# Sheet1.net
KiCad netlist of a schematic drawn in Altium Designer
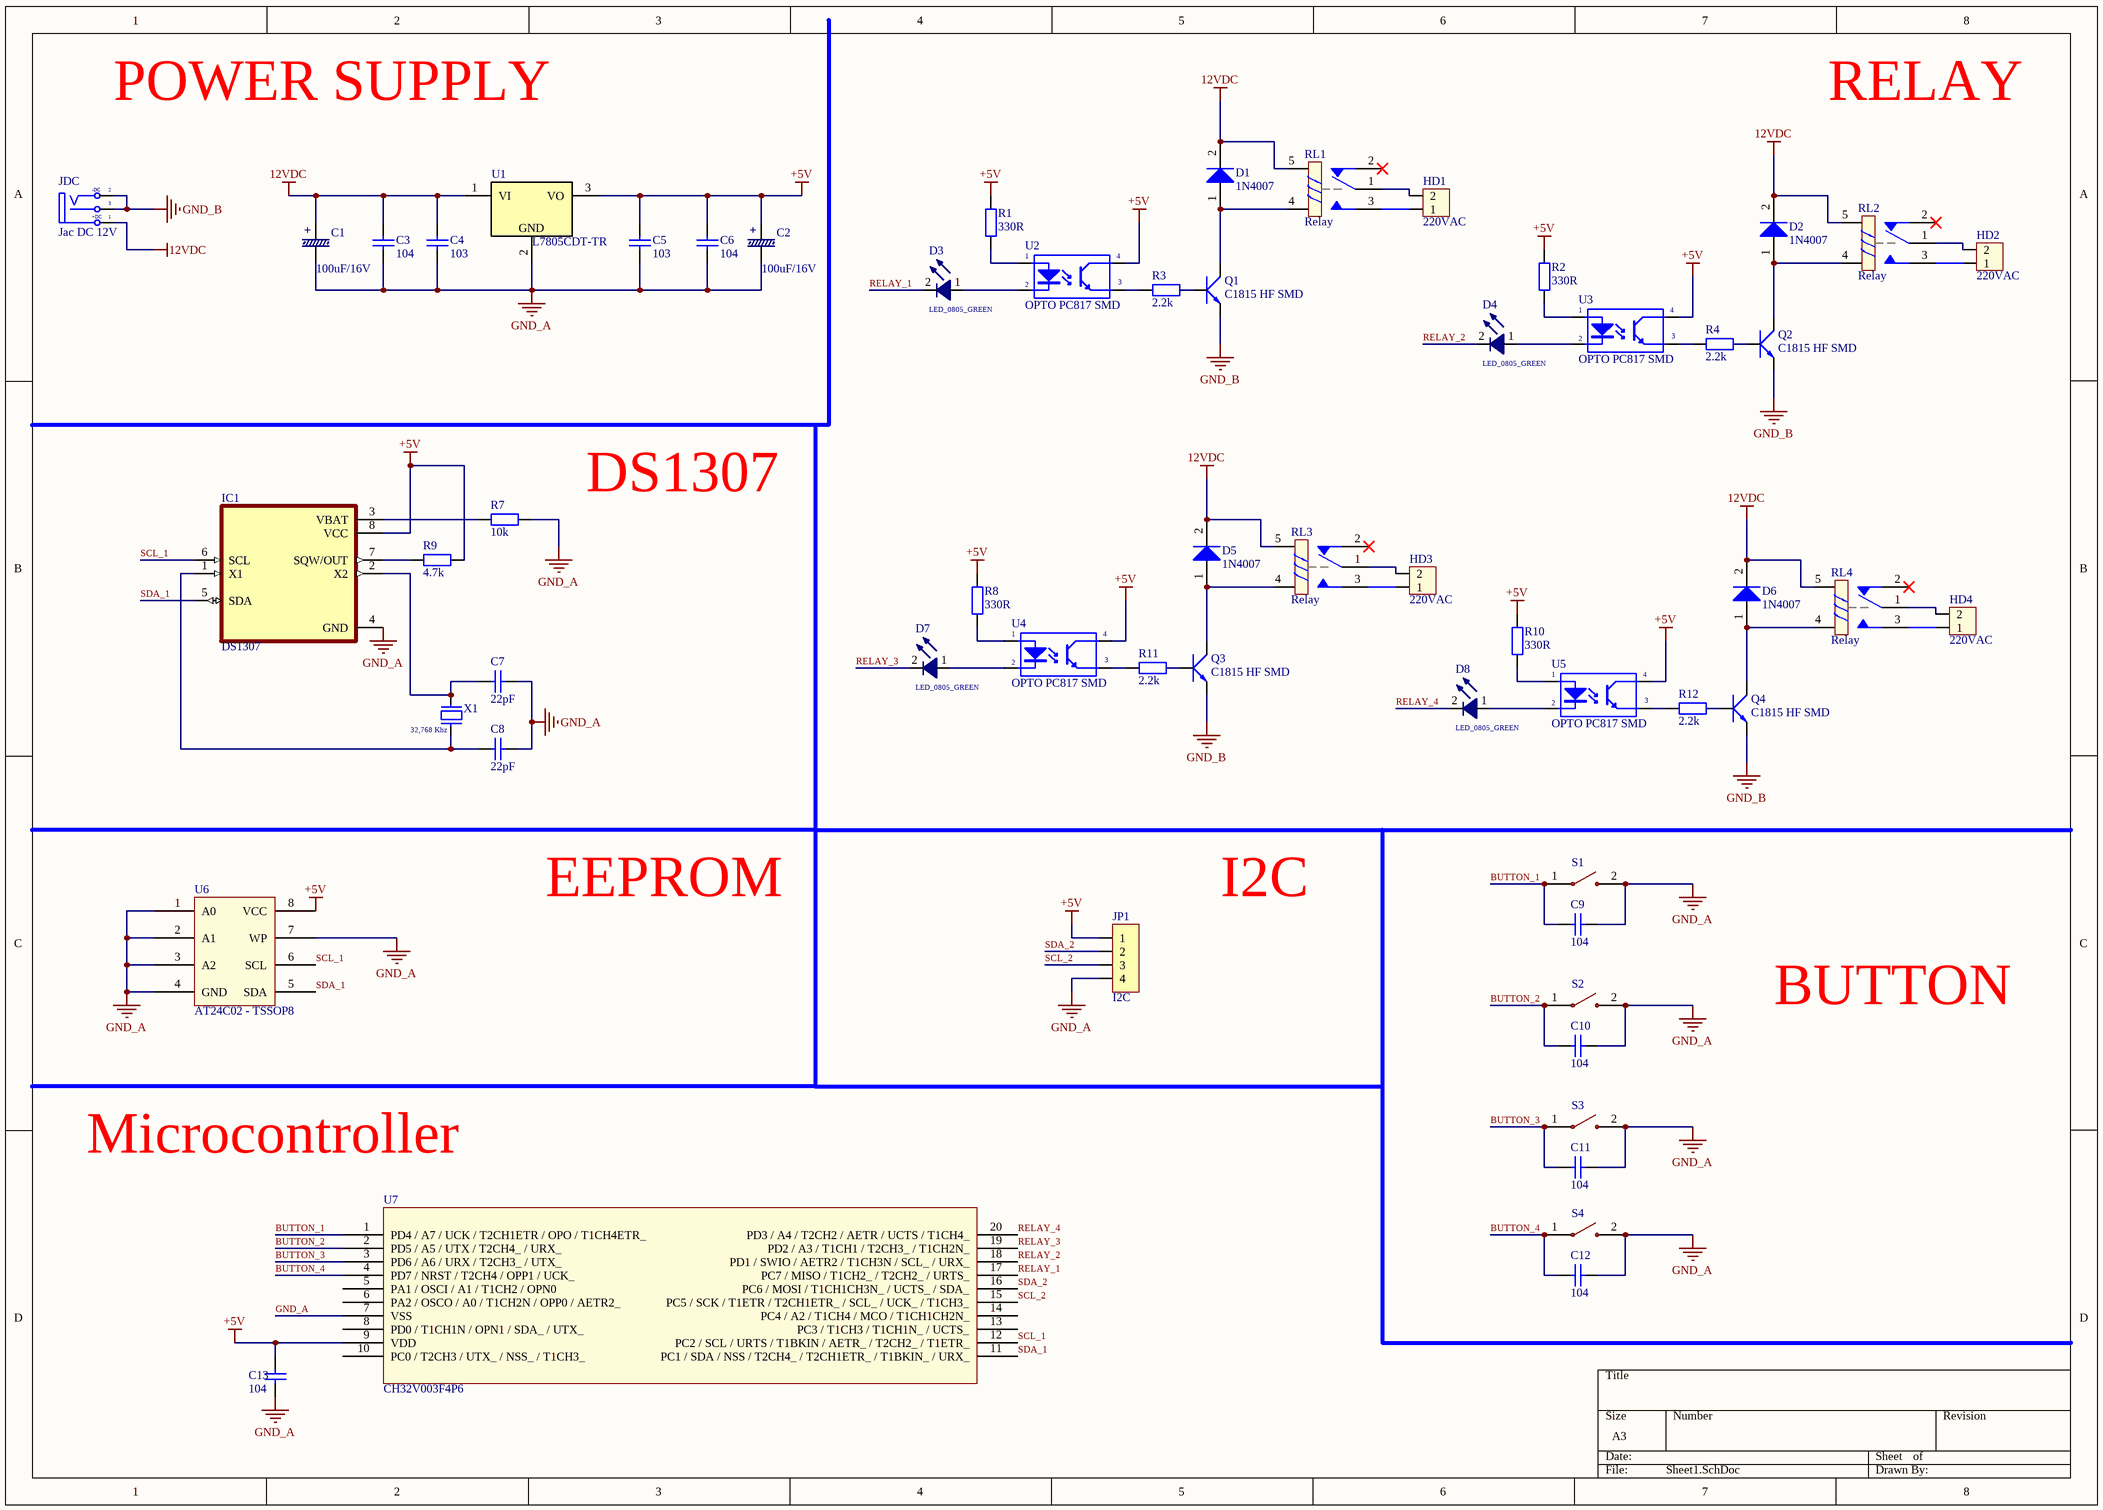
[diagram p0: Sheet1.SchDoc]

(export (version "E")
  (design (tool "Eeschema 10.0.6"))
  (components
    (comp (ref "C1")
      (value "100uF/16V")
      (footprint "ALUMINUM_7mm")
      (description "Aluminum Capacitor 100uF/16V 7mm")
      (libsource (lib "Tu dien") (part "100uF/16V"))
    )
    (comp (ref "C2")
      (value "100uF/16V")
      (footprint "ALUMINUM_7mm")
      (description "Aluminum Capacitor 100uF/16V 7mm")
      (libsource (lib "Tu dien") (part "100uF/16V"))
    )
    (comp (ref "C3")
      (value "104")
      (footprint "tu 0603")
      (description "Dán")
      (libsource (lib "Tu dien") (part "Tu 0603 104 50V 10%"))
    )
    (comp (ref "C4")
      (value "103")
      (footprint "tu 0603")
      (description "Dán")
      (libsource (lib "Tu dien") (part "Tu 0603 104 50V 10%"))
    )
    (comp (ref "C5")
      (value "103")
      (footprint "tu 0603")
      (description "Dán")
      (libsource (lib "Tu dien") (part "Tu 0603 104 50V 10%"))
    )
    (comp (ref "C6")
      (value "104")
      (footprint "tu 0603")
      (description "Dán")
      (libsource (lib "Tu dien") (part "Tu 0603 104 50V 10%"))
    )
    (comp (ref "C7")
      (value "22pF")
      (footprint "tu 1206")
      (description "Dán")
      (libsource (lib "Tu dien") (part "Tu 1206 22pF 50V 10%"))
    )
    (comp (ref "C8")
      (value "22pF")
      (footprint "tu 1206")
      (description "Dán")
      (libsource (lib "Tu dien") (part "Tu 1206 22pF 50V 10%"))
    )
    (comp (ref "C9")
      (value "104")
      (footprint "tu 0603")
      (description "Dán")
      (libsource (lib "Tu dien") (part "Tu 0603 104 50V 10%"))
    )
    (comp (ref "C10")
      (value "104")
      (footprint "tu 0603")
      (description "Dán")
      (libsource (lib "Tu dien") (part "Tu 0603 104 50V 10%"))
    )
    (comp (ref "C11")
      (value "104")
      (footprint "tu 0603")
      (description "Dán")
      (libsource (lib "Tu dien") (part "Tu 0603 104 50V 10%"))
    )
    (comp (ref "C12")
      (value "104")
      (footprint "tu 0603")
      (description "Dán")
      (libsource (lib "Tu dien") (part "Tu 0603 104 50V 10%"))
    )
    (comp (ref "C13")
      (value "104")
      (footprint "tu 0603")
      (description "Dán")
      (libsource (lib "Tu dien") (part "Tu 0603 104 50V 10%"))
    )
    (comp (ref "D1")
      (value "1N4007")
      (footprint "DIODE SMA")
      (description "Dán")
      (libsource (lib "Diode") (part "Diode M7 ( 4007 )"))
    )
    (comp (ref "D2")
      (value "1N4007")
      (footprint "DIODE SMA")
      (description "Dán")
      (libsource (lib "Diode") (part "Diode M7 ( 4007 )"))
    )
    (comp (ref "D3")
      (value "LED_0805_GREEN")
      (footprint "LED_0805_GREEN")
      (description "LED 0805 Green.")
      (libsource (lib "Led") (part "LED_0805_GREEN"))
    )
    (comp (ref "D4")
      (value "LED_0805_GREEN")
      (footprint "LED_0805_GREEN")
      (description "LED 0805 Green.")
      (libsource (lib "Led") (part "LED_0805_GREEN"))
    )
    (comp (ref "D5")
      (value "1N4007")
      (footprint "DIODE SMA")
      (description "Dán")
      (libsource (lib "Diode") (part "Diode M7 ( 4007 )"))
    )
    (comp (ref "D6")
      (value "1N4007")
      (footprint "DIODE SMA")
      (description "Dán")
      (libsource (lib "Diode") (part "Diode M7 ( 4007 )"))
    )
    (comp (ref "D7")
      (value "LED_0805_GREEN")
      (footprint "LED_0805_GREEN")
      (description "LED 0805 Green.")
      (libsource (lib "Led") (part "LED_0805_GREEN"))
    )
    (comp (ref "D8")
      (value "LED_0805_GREEN")
      (footprint "LED_0805_GREEN")
      (description "LED 0805 Green.")
      (libsource (lib "Led") (part "LED_0805_GREEN"))
    )
    (comp (ref "HD1")
      (value "220VAC")
      (footprint "HED2")
      (description "Header 2 (Green)")
      (libsource (lib "syhaunguyen") (part "Hed2"))
    )
    (comp (ref "HD2")
      (value "220VAC")
      (footprint "HED2")
      (description "Header 2 (Green)")
      (libsource (lib "syhaunguyen") (part "Hed2"))
    )
    (comp (ref "HD3")
      (value "220VAC")
      (footprint "HED2")
      (description "Header 2 (Green)")
      (libsource (lib "syhaunguyen") (part "Hed2"))
    )
    (comp (ref "HD4")
      (value "220VAC")
      (footprint "HED2")
      (description "Header 2 (Green)")
      (libsource (lib "syhaunguyen") (part "Hed2"))
    )
    (comp (ref "IC1") (value "DS1307") (footprint "DS1307") (libsource (lib "TV NQM") (part "DS1307")))
    (comp (ref "JDC")
      (value "Jac DC 12V")
      (footprint "DC-IN")
      (description "Jac DC input")
      (libsource (lib "syhaunguyen") (part "DCIN"))
    )
    (comp (ref "JP1")
      (value "I2C")
      (footprint "JP 1x4 DT")
      (description "Cắm")
      (libsource (lib "Jump") (part "JP 1x4 2.54 Duc Thang"))
    )
    (comp (ref "Q1")
      (value "C1815 HF SMD")
      (footprint "SOT23")
      (description "NPN transistor")
      (libsource (lib "TranFet") (part "C1815 HF SMD"))
    )
    (comp (ref "Q2")
      (value "C1815 HF SMD")
      (footprint "SOT23")
      (description "NPN transistor")
      (libsource (lib "TranFet") (part "C1815 HF SMD"))
    )
    (comp (ref "Q3")
      (value "C1815 HF SMD")
      (footprint "SOT23")
      (description "NPN transistor")
      (libsource (lib "TranFet") (part "C1815 HF SMD"))
    )
    (comp (ref "Q4")
      (value "C1815 HF SMD")
      (footprint "SOT23")
      (description "NPN transistor")
      (libsource (lib "TranFet") (part "C1815 HF SMD"))
    )
    (comp (ref "R1")
      (value "330R")
      (footprint "tro smd 0603")
      (description "Dán")
      (libsource (lib "Dien Tro") (part "Tro 0603 5% 330R"))
    )
    (comp (ref "R2")
      (value "330R")
      (footprint "tro smd 0603")
      (description "Dán")
      (libsource (lib "Dien Tro") (part "Tro 0603 5% 330R"))
    )
    (comp (ref "R3")
      (value "2.2k")
      (footprint "tro smd 0603")
      (description "Dán")
      (libsource (lib "Dien Tro") (part "Tro 0603 5% 2.2k"))
    )
    (comp (ref "R4")
      (value "2.2k")
      (footprint "tro smd 0603")
      (description "Dán")
      (libsource (lib "Dien Tro") (part "Tro 0603 5% 2.2k"))
    )
    (comp (ref "R7")
      (value "10k")
      (footprint "tro smd 0603")
      (description "Dán")
      (libsource (lib "Dien Tro") (part "Tro 0603 1% 10k"))
    )
    (comp (ref "R8")
      (value "330R")
      (footprint "tro smd 0603")
      (description "Dán")
      (libsource (lib "Dien Tro") (part "Tro 0603 5% 330R"))
    )
    (comp (ref "R9")
      (value "4.7k")
      (footprint "tro smd 0603")
      (description "Dán")
      (libsource (lib "Dien Tro") (part "Tro 0603 5% 4.7k"))
    )
    (comp (ref "R10")
      (value "330R")
      (footprint "tro smd 0603")
      (description "Dán")
      (libsource (lib "Dien Tro") (part "Tro 0603 5% 330R"))
    )
    (comp (ref "R11")
      (value "2.2k")
      (footprint "tro smd 0603")
      (description "Dán")
      (libsource (lib "Dien Tro") (part "Tro 0603 5% 2.2k"))
    )
    (comp (ref "R12")
      (value "2.2k")
      (footprint "tro smd 0603")
      (description "Dán")
      (libsource (lib "Dien Tro") (part "Tro 0603 5% 2.2k"))
    )
    (comp (ref "RL1")
      (value "Relay")
      (footprint "Relay 5 Chan SRD")
      (description "Relay 5 Chan")
      (libsource (lib "Component") (part "Relay 5 Chan SRD"))
    )
    (comp (ref "RL2")
      (value "Relay")
      (footprint "Relay 5 Chan SRD")
      (description "Relay 5 Chan")
      (libsource (lib "Component") (part "Relay 5 Chan SRD"))
    )
    (comp (ref "RL3")
      (value "Relay")
      (footprint "Relay 5 Chan SRD")
      (description "Relay 5 Chan")
      (libsource (lib "Component") (part "Relay 5 Chan SRD"))
    )
    (comp (ref "RL4")
      (value "Relay")
      (footprint "Relay 5 Chan SRD")
      (description "Relay 5 Chan")
      (libsource (lib "Component") (part "Relay 5 Chan SRD"))
    )
    (comp (ref "S1")
      (value "PUSH_BUTTON_SMD_3X4X2")
      (footprint "PUSH_BUTTON_SMD_3X4X2")
      (description "Push Button Tactile Switch SMD 2 Pins 3x4x2mm.")
      (libsource (lib "Buttons & Switches") (part "PUSH_BUTTON_SMD_3X4X2"))
    )
    (comp (ref "S2")
      (value "PUSH_BUTTON_SMD_3X4X2")
      (footprint "PUSH_BUTTON_SMD_3X4X2")
      (description "Push Button Tactile Switch SMD 2 Pins 3x4x2mm.")
      (libsource (lib "Buttons & Switches") (part "PUSH_BUTTON_SMD_3X4X2"))
    )
    (comp (ref "S3")
      (value "PUSH_BUTTON_SMD_3X4X2")
      (footprint "PUSH_BUTTON_SMD_3X4X2")
      (description "Push Button Tactile Switch SMD 2 Pins 3x4x2mm.")
      (libsource (lib "Buttons & Switches") (part "PUSH_BUTTON_SMD_3X4X2"))
    )
    (comp (ref "S4")
      (value "PUSH_BUTTON_SMD_3X4X2")
      (footprint "PUSH_BUTTON_SMD_3X4X2")
      (description "Push Button Tactile Switch SMD 2 Pins 3x4x2mm.")
      (libsource (lib "Buttons & Switches") (part "PUSH_BUTTON_SMD_3X4X2"))
    )
    (comp (ref "U1")
      (value "L7805CDT-TR")
      (footprint "DPAK_118_446_112X59_SMD")
      (description "Linear Voltage Regulator IC 1 Output 1.5A DPAK")
      (fields (field (name "MANUFACTURER") "Diodes"))
      (libsource (lib "IC") (part "REG_35V_5V-1.5A-7.5W-DPAK"))
    )
    (comp (ref "U2")
      (value "OPTO PC817 SMD")
      (footprint "SOP4")
      (description "Single Opto")
      (libsource (lib "IC") (part "OPTO PC817 SMD"))
    )
    (comp (ref "U3")
      (value "OPTO PC817 SMD")
      (footprint "SOP4")
      (description "Single Opto")
      (libsource (lib "IC") (part "OPTO PC817 SMD"))
    )
    (comp (ref "U4")
      (value "OPTO PC817 SMD")
      (footprint "SOP4")
      (description "Single Opto")
      (libsource (lib "IC") (part "OPTO PC817 SMD"))
    )
    (comp (ref "U5")
      (value "OPTO PC817 SMD")
      (footprint "SOP4")
      (description "Single Opto")
      (libsource (lib "IC") (part "OPTO PC817 SMD"))
    )
    (comp (ref "U6")
      (value "AT24C02 - TSSOP8")
      (footprint "AT24C02")
      (libsource (lib "TV NQM") (part "AT24C02"))
    )
    (comp (ref "U7")
      (value "CH32V003F4P6")
      (footprint "CH32V003F4P6")
      (libsource (lib "TV NQM") (part "CH32V003F4P6"))
    )
    (comp (ref "X1")
      (value "32,768 Khz")
      (footprint "XT32kn")
      (description "Crystal 32,768kHz for timer real")
      (libsource (lib "syhaunguyen") (part "XT32k"))
    )
  )
  (nets
    (net (code "1") (name "+5V") (class "Default")
      (node (ref "C13") (pin "1") (pinfunction "1_1") (pintype "passive"))
      (node (ref "C2") (pin "1") (pinfunction "1_1") (pintype "passive"))
      (node (ref "C5") (pin "1") (pinfunction "1_1") (pintype "passive"))
      (node (ref "C6") (pin "1") (pinfunction "1_1") (pintype "passive"))
      (node (ref "IC1") (pin "8") (pinfunction "VCC_8") (pintype "power_in"))
      (node (ref "JP1") (pin "1") (pinfunction "1_1") (pintype "passive"))
      (node (ref "R1") (pin "2") (pinfunction "2_2") (pintype "passive"))
      (node (ref "R10") (pin "2") (pinfunction "2_2") (pintype "passive"))
      (node (ref "R2") (pin "2") (pinfunction "2_2") (pintype "passive"))
      (node (ref "R8") (pin "2") (pinfunction "2_2") (pintype "passive"))
      (node (ref "R9") (pin "1") (pinfunction "1_1") (pintype "passive"))
      (node (ref "U1") (pin "3") (pinfunction "VO_3") (pintype "passive"))
      (node (ref "U2") (pin "4") (pinfunction "C_4") (pintype "passive"))
      (node (ref "U3") (pin "4") (pinfunction "C_4") (pintype "passive"))
      (node (ref "U4") (pin "4") (pinfunction "C_4") (pintype "passive"))
      (node (ref "U5") (pin "4") (pinfunction "C_4") (pintype "passive"))
      (node (ref "U6") (pin "8") (pinfunction "VCC_8") (pintype "passive"))
      (node (ref "U7") (pin "9") (pinfunction "VDD_9") (pintype "passive"))
    )
    (net (code "2") (name "/BUTTON_1") (class "Default")
      (node (ref "C9") (pin "2") (pinfunction "2_2") (pintype "passive"))
      (node (ref "S1") (pin "1") (pinfunction "1_1") (pintype "passive"))
      (node (ref "U7") (pin "1") (pinfunction "PD4_/_A7_/_UCK_/_T2CH1ETR_/_OPO_/_T1CH4ETR__1") (pintype "passive"))
    )
    (net (code "3") (name "/BUTTON_2") (class "Default")
      (node (ref "C10") (pin "2") (pinfunction "2_2") (pintype "passive"))
      (node (ref "S2") (pin "1") (pinfunction "1_1") (pintype "passive"))
      (node (ref "U7") (pin "2") (pinfunction "PD5_/_A5_/_UTX_/_T2CH4__/_URX__2") (pintype "passive"))
    )
    (net (code "4") (name "/BUTTON_3") (class "Default")
      (node (ref "C11") (pin "2") (pinfunction "2_2") (pintype "passive"))
      (node (ref "S3") (pin "1") (pinfunction "1_1") (pintype "passive"))
      (node (ref "U7") (pin "3") (pinfunction "PD6_/_A6_/_URX_/_T2CH3__/_UTX__3") (pintype "passive"))
    )
    (net (code "5") (name "/BUTTON_4") (class "Default")
      (node (ref "C12") (pin "2") (pinfunction "2_2") (pintype "passive"))
      (node (ref "S4") (pin "1") (pinfunction "1_1") (pintype "passive"))
      (node (ref "U7") (pin "4") (pinfunction "PD7_/_NRST_/_T2CH4_/_OPP1_/_UCK__4") (pintype "passive"))
    )
    (net (code "6") (name "/RELAY_1") (class "Default")
      (node (ref "D3") (pin "2") (pinfunction "2_2") (pintype "passive"))
      (node (ref "U7") (pin "17") (pinfunction "PC7_/_MISO_/_T1CH2__/_T2CH2__/_URTS__17") (pintype "passive"))
    )
    (net (code "7") (name "/RELAY_2") (class "Default")
      (node (ref "D4") (pin "2") (pinfunction "2_2") (pintype "passive"))
      (node (ref "U7") (pin "18") (pinfunction "PD1_/_SWIO_/_AETR2_/_T1CH3N_/_SCL__/_URX__18") (pintype "passive"))
    )
    (net (code "8") (name "/RELAY_3") (class "Default")
      (node (ref "D7") (pin "2") (pinfunction "2_2") (pintype "passive"))
      (node (ref "U7") (pin "19") (pinfunction "PD2_/_A3_/_T1CH1_/_T2CH3__/_T1CH2N__19") (pintype "passive"))
    )
    (net (code "9") (name "/RELAY_4") (class "Default")
      (node (ref "D8") (pin "2") (pinfunction "2_2") (pintype "passive"))
      (node (ref "U7") (pin "20") (pinfunction "PD3_/_A4_/_T2CH2_/_AETR_/_UCTS_/_T1CH4__20") (pintype "passive"))
    )
    (net (code "10") (name "/SCL_1") (class "Default")
      (node (ref "IC1") (pin "6") (pinfunction "SCL_6") (pintype "input"))
      (node (ref "U6") (pin "6") (pinfunction "SCL_6") (pintype "passive"))
      (node (ref "U7") (pin "12") (pinfunction "PC2_/_SCL_/_URTS_/_T1BKIN_/_AETR__/_T2CH2__/_T1ETR__12") (pintype "passive"))
    )
    (net (code "11") (name "/SCL_2") (class "Default")
      (node (ref "JP1") (pin "3") (pinfunction "3_3") (pintype "passive"))
      (node (ref "U7") (pin "15") (pinfunction "PC5_/_SCK_/_T1ETR_/_T2CH1ETR__/_SCL__/_UCK__/_T1CH3__15") (pintype "passive"))
    )
    (net (code "12") (name "/SDA_1") (class "Default")
      (node (ref "IC1") (pin "5") (pinfunction "SDA_5") (pintype "bidirectional"))
      (node (ref "U6") (pin "5") (pinfunction "SDA_5") (pintype "passive"))
      (node (ref "U7") (pin "11") (pinfunction "PC1_/_SDA_/_NSS_/_T2CH4__/_T2CH1ETR__/_T1BKIN__/_URX__11") (pintype "passive"))
    )
    (net (code "13") (name "/SDA_2") (class "Default")
      (node (ref "JP1") (pin "2") (pinfunction "2_2") (pintype "passive"))
      (node (ref "U7") (pin "16") (pinfunction "PC6_/_MOSI_/_T1CH1CH3N__/_UCTS__/_SDA__16") (pintype "passive"))
    )
    (net (code "14") (name "12VDC") (class "Default")
      (node (ref "C1") (pin "1") (pinfunction "1_1") (pintype "passive"))
      (node (ref "C3") (pin "1") (pinfunction "1_1") (pintype "passive"))
      (node (ref "C4") (pin "1") (pinfunction "1_1") (pintype "passive"))
      (node (ref "D1") (pin "2") (pinfunction "K_2") (pintype "passive"))
      (node (ref "D2") (pin "2") (pinfunction "K_2") (pintype "passive"))
      (node (ref "D5") (pin "2") (pinfunction "K_2") (pintype "passive"))
      (node (ref "D6") (pin "2") (pinfunction "K_2") (pintype "passive"))
      (node (ref "JDC") (pin "1") (pinfunction "T_1") (pintype "passive"))
      (node (ref "RL1") (pin "5") (pinfunction "5_5") (pintype "passive"))
      (node (ref "RL2") (pin "5") (pinfunction "5_5") (pintype "passive"))
      (node (ref "RL3") (pin "5") (pinfunction "5_5") (pintype "passive"))
      (node (ref "RL4") (pin "5") (pinfunction "5_5") (pintype "passive"))
      (node (ref "U1") (pin "1") (pinfunction "VI_1") (pintype "passive"))
    )
    (net (code "15") (name "GND_A") (class "Default")
      (node (ref "C1") (pin "2") (pinfunction "2_2") (pintype "passive"))
      (node (ref "C10") (pin "1") (pinfunction "1_1") (pintype "passive"))
      (node (ref "C11") (pin "1") (pinfunction "1_1") (pintype "passive"))
      (node (ref "C12") (pin "1") (pinfunction "1_1") (pintype "passive"))
      (node (ref "C13") (pin "2") (pinfunction "2_2") (pintype "passive"))
      (node (ref "C2") (pin "2") (pinfunction "2_2") (pintype "passive"))
      (node (ref "C3") (pin "2") (pinfunction "2_2") (pintype "passive"))
      (node (ref "C4") (pin "2") (pinfunction "2_2") (pintype "passive"))
      (node (ref "C5") (pin "2") (pinfunction "2_2") (pintype "passive"))
      (node (ref "C6") (pin "2") (pinfunction "2_2") (pintype "passive"))
      (node (ref "C7") (pin "2") (pinfunction "2_2") (pintype "passive"))
      (node (ref "C8") (pin "2") (pinfunction "2_2") (pintype "passive"))
      (node (ref "C9") (pin "1") (pinfunction "1_1") (pintype "passive"))
      (node (ref "IC1") (pin "4") (pinfunction "GND_4") (pintype "power_in"))
      (node (ref "JP1") (pin "4") (pinfunction "4_4") (pintype "passive"))
      (node (ref "R7") (pin "2") (pinfunction "2_2") (pintype "passive"))
      (node (ref "S1") (pin "2") (pinfunction "2_2") (pintype "passive"))
      (node (ref "S2") (pin "2") (pinfunction "2_2") (pintype "passive"))
      (node (ref "S3") (pin "2") (pinfunction "2_2") (pintype "passive"))
      (node (ref "S4") (pin "2") (pinfunction "2_2") (pintype "passive"))
      (node (ref "U1") (pin "2") (pintype "passive"))
      (node (ref "U6") (pin "1") (pinfunction "A0_1") (pintype "passive"))
      (node (ref "U6") (pin "2") (pinfunction "A1_2") (pintype "passive"))
      (node (ref "U6") (pin "3") (pinfunction "A2_3") (pintype "passive"))
      (node (ref "U6") (pin "4") (pinfunction "GND_4") (pintype "passive"))
      (node (ref "U6") (pin "7") (pinfunction "WP_7") (pintype "passive"))
      (node (ref "U7") (pin "7") (pinfunction "VSS_7") (pintype "passive"))
    )
    (net (code "16") (name "GND_B") (class "Default")
      (node (ref "JDC") (pin "2") (pinfunction "TN_2") (pintype "passive"))
      (node (ref "JDC") (pin "3") (pinfunction "S_3") (pintype "power_in"))
      (node (ref "Q1") (pin "2") (pinfunction "E_2") (pintype "passive"))
      (node (ref "Q2") (pin "2") (pinfunction "E_2") (pintype "passive"))
      (node (ref "Q3") (pin "2") (pinfunction "E_2") (pintype "passive"))
      (node (ref "Q4") (pin "2") (pinfunction "E_2") (pintype "passive"))
    )
    (net (code "17") (name "Net-(D1-A)") (class "Default")
      (node (ref "D1") (pin "1") (pinfunction "A_1") (pintype "passive"))
      (node (ref "Q1") (pin "3") (pinfunction "C_3") (pintype "passive"))
      (node (ref "RL1") (pin "4") (pinfunction "4_4") (pintype "passive"))
    )
    (net (code "18") (name "Net-(D2-A)") (class "Default")
      (node (ref "D2") (pin "1") (pinfunction "A_1") (pintype "passive"))
      (node (ref "Q2") (pin "3") (pinfunction "C_3") (pintype "passive"))
      (node (ref "RL2") (pin "4") (pinfunction "4_4") (pintype "passive"))
    )
    (net (code "19") (name "Net-(D5-A)") (class "Default")
      (node (ref "D5") (pin "1") (pinfunction "A_1") (pintype "passive"))
      (node (ref "Q3") (pin "3") (pinfunction "C_3") (pintype "passive"))
      (node (ref "RL3") (pin "4") (pinfunction "4_4") (pintype "passive"))
    )
    (net (code "20") (name "Net-(D6-A)") (class "Default")
      (node (ref "D6") (pin "1") (pinfunction "A_1") (pintype "passive"))
      (node (ref "Q4") (pin "3") (pinfunction "C_3") (pintype "passive"))
      (node (ref "RL4") (pin "4") (pinfunction "4_4") (pintype "passive"))
    )
    (net (code "21") (name "Net-(HD1-Pad1)") (class "Default")
      (node (ref "HD1") (pin "1") (pinfunction "1_1") (pintype "passive"))
      (node (ref "RL1") (pin "3") (pinfunction "3_3") (pintype "passive"))
    )
    (net (code "22") (name "Net-(HD1-Pad2)") (class "Default")
      (node (ref "HD1") (pin "2") (pinfunction "2_2") (pintype "passive"))
      (node (ref "RL1") (pin "1") (pinfunction "1_1") (pintype "passive"))
    )
    (net (code "23") (name "Net-(HD2-Pad1)") (class "Default")
      (node (ref "HD2") (pin "1") (pinfunction "1_1") (pintype "passive"))
      (node (ref "RL2") (pin "3") (pinfunction "3_3") (pintype "passive"))
    )
    (net (code "24") (name "Net-(HD2-Pad2)") (class "Default")
      (node (ref "HD2") (pin "2") (pinfunction "2_2") (pintype "passive"))
      (node (ref "RL2") (pin "1") (pinfunction "1_1") (pintype "passive"))
    )
    (net (code "25") (name "Net-(HD3-Pad1)") (class "Default")
      (node (ref "HD3") (pin "1") (pinfunction "1_1") (pintype "passive"))
      (node (ref "RL3") (pin "3") (pinfunction "3_3") (pintype "passive"))
    )
    (net (code "26") (name "Net-(HD3-Pad2)") (class "Default")
      (node (ref "HD3") (pin "2") (pinfunction "2_2") (pintype "passive"))
      (node (ref "RL3") (pin "1") (pinfunction "1_1") (pintype "passive"))
    )
    (net (code "27") (name "Net-(HD4-Pad1)") (class "Default")
      (node (ref "HD4") (pin "1") (pinfunction "1_1") (pintype "passive"))
      (node (ref "RL4") (pin "3") (pinfunction "3_3") (pintype "passive"))
    )
    (net (code "28") (name "Net-(HD4-Pad2)") (class "Default")
      (node (ref "HD4") (pin "2") (pinfunction "2_2") (pintype "passive"))
      (node (ref "RL4") (pin "1") (pinfunction "1_1") (pintype "passive"))
    )
    (net (code "29") (name "Net-(IC1-SQW{slash}OUT)") (class "Default")
      (node (ref "IC1") (pin "7") (pinfunction "SQW/OUT_7") (pintype "output"))
      (node (ref "R9") (pin "2") (pinfunction "2_2") (pintype "passive"))
    )
    (net (code "30") (name "Net-(IC1-VBAT)") (class "Default")
      (node (ref "IC1") (pin "3") (pinfunction "VBAT_3") (pintype "power_in"))
      (node (ref "R7") (pin "1") (pinfunction "1_1") (pintype "passive"))
    )
    (net (code "31") (name "Net-(IC1-X1)") (class "Default")
      (node (ref "C8") (pin "1") (pinfunction "1_1") (pintype "passive"))
      (node (ref "IC1") (pin "1") (pinfunction "X1_1") (pintype "input"))
      (node (ref "X1") (pin "1") (pinfunction "1_1") (pintype "passive"))
    )
    (net (code "32") (name "Net-(IC1-X2)") (class "Default")
      (node (ref "C7") (pin "1") (pinfunction "1_1") (pintype "passive"))
      (node (ref "IC1") (pin "2") (pinfunction "X2_2") (pintype "output"))
      (node (ref "X1") (pin "2") (pinfunction "2_2") (pintype "passive"))
    )
    (net (code "33") (name "Net-(Q1-B)") (class "Default")
      (node (ref "Q1") (pin "1") (pinfunction "B_1") (pintype "passive"))
      (node (ref "R3") (pin "2") (pinfunction "2_2") (pintype "passive"))
    )
    (net (code "34") (name "Net-(Q2-B)") (class "Default")
      (node (ref "Q2") (pin "1") (pinfunction "B_1") (pintype "passive"))
      (node (ref "R4") (pin "2") (pinfunction "2_2") (pintype "passive"))
    )
    (net (code "35") (name "Net-(Q3-B)") (class "Default")
      (node (ref "Q3") (pin "1") (pinfunction "B_1") (pintype "passive"))
      (node (ref "R11") (pin "2") (pinfunction "2_2") (pintype "passive"))
    )
    (net (code "36") (name "Net-(Q4-B)") (class "Default")
      (node (ref "Q4") (pin "1") (pinfunction "B_1") (pintype "passive"))
      (node (ref "R12") (pin "2") (pinfunction "2_2") (pintype "passive"))
    )
    (net (code "37") (name "Net-(U2-A)") (class "Default")
      (node (ref "R1") (pin "1") (pinfunction "1_1") (pintype "passive"))
      (node (ref "U2") (pin "1") (pinfunction "A_1") (pintype "passive"))
    )
    (net (code "38") (name "Net-(U2-E)") (class "Default")
      (node (ref "R3") (pin "1") (pinfunction "1_1") (pintype "passive"))
      (node (ref "U2") (pin "3") (pinfunction "E_3") (pintype "passive"))
    )
    (net (code "39") (name "Net-(U2-K)") (class "Default")
      (node (ref "D3") (pin "1") (pinfunction "1_1") (pintype "passive"))
      (node (ref "U2") (pin "2") (pinfunction "K_2") (pintype "passive"))
    )
    (net (code "40") (name "Net-(U3-A)") (class "Default")
      (node (ref "R2") (pin "1") (pinfunction "1_1") (pintype "passive"))
      (node (ref "U3") (pin "1") (pinfunction "A_1") (pintype "passive"))
    )
    (net (code "41") (name "Net-(U3-E)") (class "Default")
      (node (ref "R4") (pin "1") (pinfunction "1_1") (pintype "passive"))
      (node (ref "U3") (pin "3") (pinfunction "E_3") (pintype "passive"))
    )
    (net (code "42") (name "Net-(U3-K)") (class "Default")
      (node (ref "D4") (pin "1") (pinfunction "1_1") (pintype "passive"))
      (node (ref "U3") (pin "2") (pinfunction "K_2") (pintype "passive"))
    )
    (net (code "43") (name "Net-(U4-A)") (class "Default")
      (node (ref "R8") (pin "1") (pinfunction "1_1") (pintype "passive"))
      (node (ref "U4") (pin "1") (pinfunction "A_1") (pintype "passive"))
    )
    (net (code "44") (name "Net-(U4-E)") (class "Default")
      (node (ref "R11") (pin "1") (pinfunction "1_1") (pintype "passive"))
      (node (ref "U4") (pin "3") (pinfunction "E_3") (pintype "passive"))
    )
    (net (code "45") (name "Net-(U4-K)") (class "Default")
      (node (ref "D7") (pin "1") (pinfunction "1_1") (pintype "passive"))
      (node (ref "U4") (pin "2") (pinfunction "K_2") (pintype "passive"))
    )
    (net (code "46") (name "Net-(U5-A)") (class "Default")
      (node (ref "R10") (pin "1") (pinfunction "1_1") (pintype "passive"))
      (node (ref "U5") (pin "1") (pinfunction "A_1") (pintype "passive"))
    )
    (net (code "47") (name "Net-(U5-E)") (class "Default")
      (node (ref "R12") (pin "1") (pinfunction "1_1") (pintype "passive"))
      (node (ref "U5") (pin "3") (pinfunction "E_3") (pintype "passive"))
    )
    (net (code "48") (name "Net-(U5-K)") (class "Default")
      (node (ref "D8") (pin "1") (pinfunction "1_1") (pintype "passive"))
      (node (ref "U5") (pin "2") (pinfunction "K_2") (pintype "passive"))
    )
    (net (code "49") (name "unconnected-(RL1-Pad2)") (class "Default")
      (node (ref "RL1") (pin "2") (pinfunction "2_2") (pintype "passive+no_connect"))
    )
    (net (code "50") (name "unconnected-(RL2-Pad2)") (class "Default")
      (node (ref "RL2") (pin "2") (pinfunction "2_2") (pintype "passive+no_connect"))
    )
    (net (code "51") (name "unconnected-(RL3-Pad2)") (class "Default")
      (node (ref "RL3") (pin "2") (pinfunction "2_2") (pintype "passive+no_connect"))
    )
    (net (code "52") (name "unconnected-(RL4-Pad2)") (class "Default")
      (node (ref "RL4") (pin "2") (pinfunction "2_2") (pintype "passive+no_connect"))
    )
    (net (code "53") (name "unconnected-(U7-PA1_{slash}_OSCI_{slash}_A1_{slash}_T1CH2_{slash}_OPN0-Pad5)") (class "Default")
      (node (ref "U7") (pin "5") (pinfunction "PA1_/_OSCI_/_A1_/_T1CH2_/_OPN0_5") (pintype "passive"))
    )
    (net (code "54") (name "unconnected-(U7-PA2_{slash}_OSCO_{slash}_A0_{slash}_T1CH2N_{slash}_OPP0_{slash}_AETR2_-Pad6)") (class "Default")
      (node (ref "U7") (pin "6") (pinfunction "PA2_/_OSCO_/_A0_/_T1CH2N_/_OPP0_/_AETR2__6") (pintype "passive"))
    )
    (net (code "55") (name "unconnected-(U7-PC0_{slash}_T2CH3_{slash}_UTX__{slash}_NSS__{slash}_T1CH3_-Pad10)") (class "Default")
      (node (ref "U7") (pin "10") (pinfunction "PC0_/_T2CH3_/_UTX__/_NSS__/_T1CH3__10") (pintype "passive"))
    )
    (net (code "56") (name "unconnected-(U7-PC3_{slash}_T1CH3_{slash}_T1CH1N__{slash}_UCTS_-Pad13)") (class "Default")
      (node (ref "U7") (pin "13") (pinfunction "PC3_/_T1CH3_/_T1CH1N__/_UCTS__13") (pintype "passive"))
    )
    (net (code "57") (name "unconnected-(U7-PC4_{slash}_A2_{slash}_T1CH4_{slash}_MCO_{slash}_T1CH1CH2N_-Pad14)") (class "Default")
      (node (ref "U7") (pin "14") (pinfunction "PC4_/_A2_/_T1CH4_/_MCO_/_T1CH1CH2N__14") (pintype "passive"))
    )
    (net (code "58") (name "unconnected-(U7-PD0_{slash}_T1CH1N_{slash}_OPN1_{slash}_SDA__{slash}_UTX_-Pad8)") (class "Default")
      (node (ref "U7") (pin "8") (pinfunction "PD0_/_T1CH1N_/_OPN1_/_SDA__/_UTX__8") (pintype "passive"))
    )
  )
)
